# CM3_HDMI.net
KiCad netlist of a schematic drawn in Altium Designer
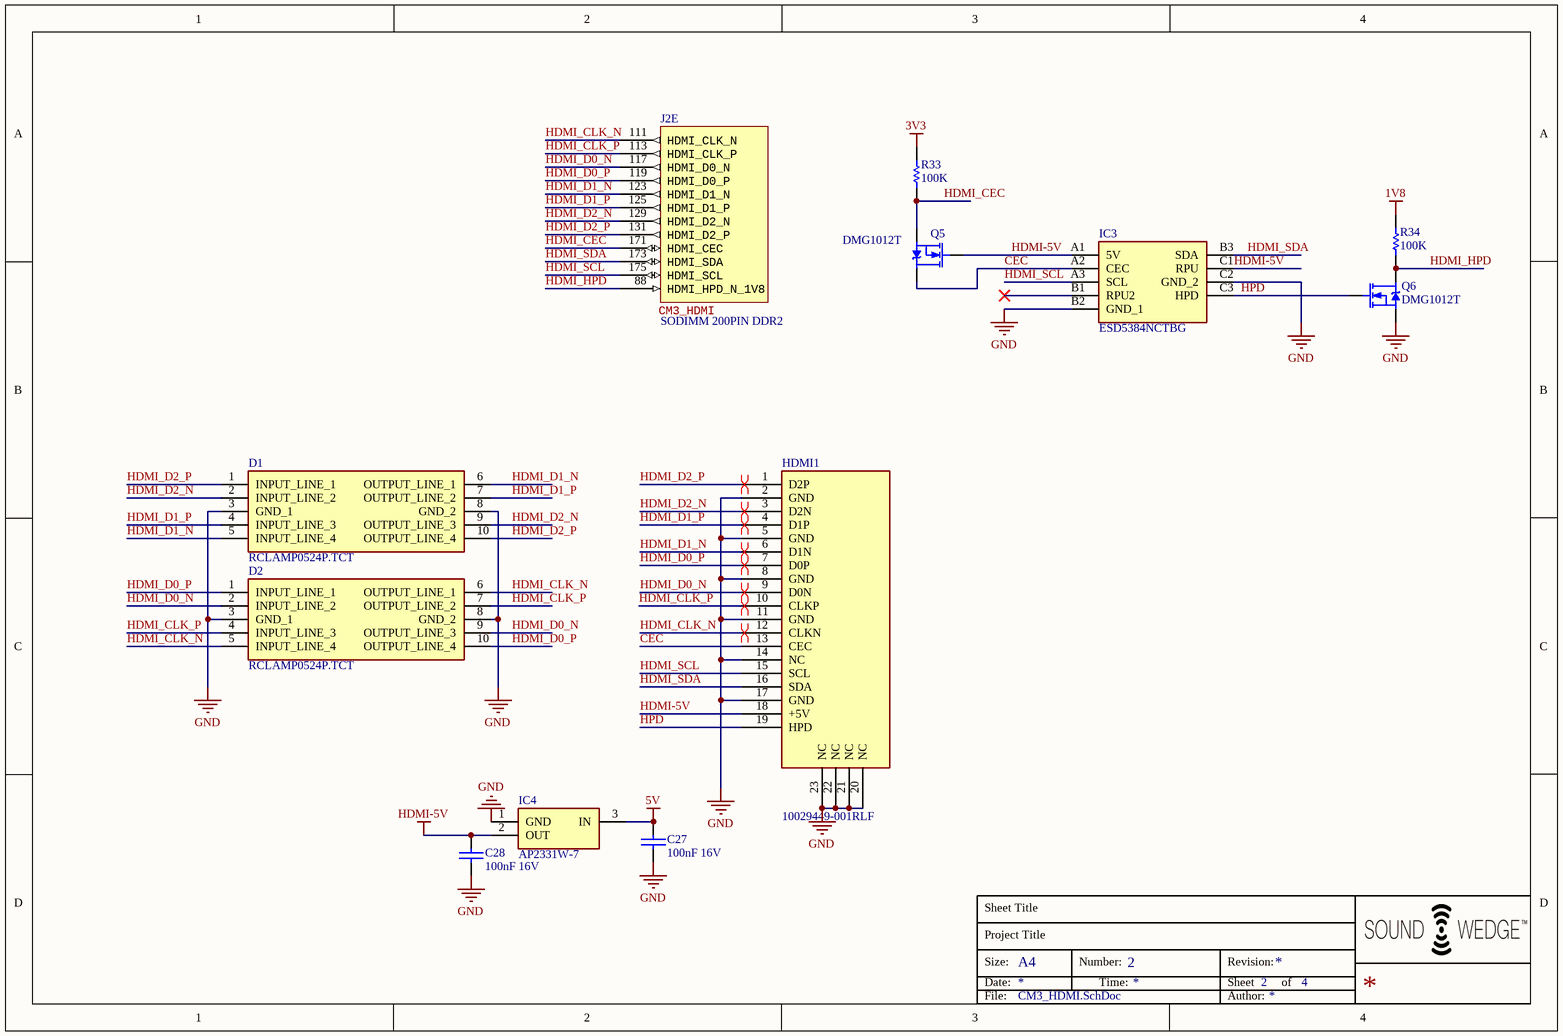
[diagram p0: CM3_HDMI.SchDoc]

(export (version "E")
  (design (tool "Eeschema 10.0.6"))
  (components
    (comp (ref "C27") (value "100nF 16V") (footprint "PCB_VPlayer:0402C") (libsource (lib "电容") (part "CAP")))
    (comp (ref "C28") (value "100nF 16V") (footprint "PCB_VPlayer:0402C") (libsource (lib "电容") (part "CAP")))
    (comp (ref "D1")
      (value "RCLAMP0524P.TCT")
      (footprint "SamacSys:RCLAMP0524P")
      (description "Diode")
      (fields (field (name "MOUSER PART NUMBER") "947-RCLAMP0524P.TCT"))
      (libsource (lib "*") (part "RCLAMP0524P.TCT"))
    )
    (comp (ref "D2")
      (value "RCLAMP0524P.TCT")
      (footprint "SamacSys:RCLAMP0524P")
      (description "Diode")
      (fields (field (name "MOUSER PART NUMBER") "947-RCLAMP0524P.TCT"))
      (libsource (lib "*") (part "RCLAMP0524P.TCT"))
    )
    (comp (ref "HDMI1")
      (value "10029449-001RLF")
      (footprint "HDMI-001")
      (description "HDMI Connector")
      (fields
        (field (name "MOUSER PART NUMBER") "649-10029449-001RLF")
        (field (name "RS PART NUMBER") "7710094")
      )
      (libsource (lib "音视频插座") (part "10029449-001RLF"))
    )
    (comp (ref "IC3")
      (value "ESD5384NCTBG")
      (footprint "SamacSys:BGA9C40P3X3_114X114X63")
      (description "Integrated Circuit")
      (fields
        (field (name "MOUSER PART NUMBER") "863-ESD5384NCTBG")
        (field (name "RS PART NUMBER") "8010213P")
      )
      (libsource (lib "*") (part "ESD5384NCTBG"))
    )
    (comp (ref "IC4")
      (value "AP2331W-7")
      (footprint "SamacSys:SOT95P285X130-3N")
      (description "Integrated Circuit")
      (fields (field (name "MOUSER PART NUMBER") "621-AP2331W-7") (field (name "RS PART NUMBER") "8287665P"))
      (libsource (lib "*") (part "AP2331W-7"))
    )
    (comp (ref "J2")
      (value "SODIMM 200PIN DDR2")
      (footprint "树莓派模块:SODIMM 200PIN - 5.2H")
      (libsource (lib "树莓派模块") (part "RPi-CM3"))
    )
    (comp (ref "Q5")
      (value "DMG1012T")
      (footprint "SOT523")
      (description "N沟道场效应管")
      (libsource (lib "MOS管") (part "N-MOS"))
    )
    (comp (ref "Q6")
      (value "DMG1012T")
      (footprint "SOT523")
      (description "N沟道场效应管")
      (libsource (lib "MOS管") (part "N-MOS"))
    )
    (comp (ref "R33") (value "100K") (footprint "PCB_VPlayer:0402R") (libsource (lib "电阻") (part "RES")))
    (comp (ref "R34") (value "100K") (footprint "PCB_VPlayer:0402R") (libsource (lib "电阻") (part "RES")))
  )
  (nets
    (net (code "1") (name "/CEC") (class "Default")
      (node (ref "HDMI1") (pin "13") (pinfunction "CEC_13") (pintype "passive"))
      (node (ref "IC3") (pin "A2") (pinfunction "CEC_A2") (pintype "passive"))
      (node (ref "Q5") (pin "D") (pinfunction "D_D") (pintype "passive"))
    )
    (net (code "2") (name "/HDMI_CEC") (class "Default")
      (node (ref "J2") (pin "171") (pinfunction "HDMI_CEC_171") (pintype "bidirectional"))
      (node (ref "Q5") (pin "S") (pinfunction "S_S") (pintype "passive"))
      (node (ref "R33") (pin "1") (pinfunction "1_1") (pintype "passive"))
    )
    (net (code "3") (name "/HDMI_CLK_N") (class "Default")
      (node (ref "D2") (pin "5") (pinfunction "INPUT_LINE_4_5") (pintype "passive"))
      (node (ref "D2") (pin "6") (pinfunction "OUTPUT_LINE_1_6") (pintype "passive"))
      (node (ref "HDMI1") (pin "12") (pinfunction "CLKN_12") (pintype "passive"))
      (node (ref "J2") (pin "111") (pinfunction "HDMI_CLK_N_111") (pintype "output"))
    )
    (net (code "4") (name "/HDMI_CLK_P") (class "Default")
      (node (ref "D2") (pin "4") (pinfunction "INPUT_LINE_3_4") (pintype "passive"))
      (node (ref "D2") (pin "7") (pinfunction "OUTPUT_LINE_2_7") (pintype "passive"))
      (node (ref "HDMI1") (pin "10") (pinfunction "CLKP_10") (pintype "passive"))
      (node (ref "J2") (pin "113") (pinfunction "HDMI_CLK_P_113") (pintype "output"))
    )
    (net (code "5") (name "/HDMI_D0_N") (class "Default")
      (node (ref "D2") (pin "2") (pinfunction "INPUT_LINE_2_2") (pintype "passive"))
      (node (ref "D2") (pin "9") (pinfunction "OUTPUT_LINE_3_9") (pintype "passive"))
      (node (ref "HDMI1") (pin "9") (pinfunction "D0N_9") (pintype "passive"))
      (node (ref "J2") (pin "117") (pinfunction "HDMI_D0_N_117") (pintype "output"))
    )
    (net (code "6") (name "/HDMI_D0_P") (class "Default")
      (node (ref "D2") (pin "1") (pinfunction "INPUT_LINE_1_1") (pintype "passive"))
      (node (ref "D2") (pin "10") (pinfunction "OUTPUT_LINE_4_10") (pintype "passive"))
      (node (ref "HDMI1") (pin "7") (pinfunction "D0P_7") (pintype "passive"))
      (node (ref "J2") (pin "119") (pinfunction "HDMI_D0_P_119") (pintype "output"))
    )
    (net (code "7") (name "/HDMI_D1_N") (class "Default")
      (node (ref "D1") (pin "5") (pinfunction "INPUT_LINE_4_5") (pintype "passive"))
      (node (ref "D1") (pin "6") (pinfunction "OUTPUT_LINE_1_6") (pintype "passive"))
      (node (ref "HDMI1") (pin "6") (pinfunction "D1N_6") (pintype "passive"))
      (node (ref "J2") (pin "123") (pinfunction "HDMI_D1_N_123") (pintype "output"))
    )
    (net (code "8") (name "/HDMI_D1_P") (class "Default")
      (node (ref "D1") (pin "4") (pinfunction "INPUT_LINE_3_4") (pintype "passive"))
      (node (ref "D1") (pin "7") (pinfunction "OUTPUT_LINE_2_7") (pintype "passive"))
      (node (ref "HDMI1") (pin "4") (pinfunction "D1P_4") (pintype "passive"))
      (node (ref "J2") (pin "125") (pinfunction "HDMI_D1_P_125") (pintype "output"))
    )
    (net (code "9") (name "/HDMI_D2_N") (class "Default")
      (node (ref "D1") (pin "2") (pinfunction "INPUT_LINE_2_2") (pintype "passive"))
      (node (ref "D1") (pin "9") (pinfunction "OUTPUT_LINE_3_9") (pintype "passive"))
      (node (ref "HDMI1") (pin "3") (pinfunction "D2N_3") (pintype "passive"))
      (node (ref "J2") (pin "129") (pinfunction "HDMI_D2_N_129") (pintype "output"))
    )
    (net (code "10") (name "/HDMI_D2_P") (class "Default")
      (node (ref "D1") (pin "1") (pinfunction "INPUT_LINE_1_1") (pintype "passive"))
      (node (ref "D1") (pin "10") (pinfunction "OUTPUT_LINE_4_10") (pintype "passive"))
      (node (ref "HDMI1") (pin "1") (pinfunction "D2P_1") (pintype "passive"))
      (node (ref "J2") (pin "131") (pinfunction "HDMI_D2_P_131") (pintype "output"))
    )
    (net (code "11") (name "/HDMI_HPD") (class "Default")
      (node (ref "J2") (pin "88") (pinfunction "HDMI_HPD_N_1V8_88") (pintype "input"))
      (node (ref "Q6") (pin "D") (pinfunction "D_D") (pintype "passive"))
      (node (ref "R34") (pin "1") (pinfunction "1_1") (pintype "passive"))
    )
    (net (code "12") (name "/HDMI_SCL") (class "Default")
      (node (ref "HDMI1") (pin "15") (pinfunction "SCL_15") (pintype "passive"))
      (node (ref "IC3") (pin "A3") (pinfunction "SCL_A3") (pintype "passive"))
      (node (ref "J2") (pin "175") (pinfunction "HDMI_SCL_175") (pintype "bidirectional"))
    )
    (net (code "13") (name "/HDMI_SDA") (class "Default")
      (node (ref "HDMI1") (pin "16") (pinfunction "SDA_16") (pintype "passive"))
      (node (ref "IC3") (pin "B3") (pinfunction "SDA_B3") (pintype "passive"))
      (node (ref "J2") (pin "173") (pinfunction "HDMI_SDA_173") (pintype "bidirectional"))
    )
    (net (code "14") (name "/HPD") (class "Default")
      (node (ref "HDMI1") (pin "19") (pinfunction "HPD_19") (pintype "passive"))
      (node (ref "IC3") (pin "C3") (pinfunction "HPD_C3") (pintype "passive"))
      (node (ref "Q6") (pin "G") (pinfunction "G_G") (pintype "passive"))
    )
    (net (code "15") (name "1V8") (class "Default")
      (node (ref "R34") (pin "2") (pinfunction "2_2") (pintype "passive"))
    )
    (net (code "16") (name "3V3") (class "Default")
      (node (ref "R33") (pin "2") (pinfunction "2_2") (pintype "passive"))
    )
    (net (code "17") (name "5V") (class "Default")
      (node (ref "C27") (pin "1") (pinfunction "1_1") (pintype "passive"))
      (node (ref "IC4") (pin "3") (pinfunction "IN_3") (pintype "passive"))
    )
    (net (code "18") (name "GND") (class "Default")
      (node (ref "C27") (pin "2") (pinfunction "2_2") (pintype "passive"))
      (node (ref "C28") (pin "2") (pinfunction "2_2") (pintype "passive"))
      (node (ref "D1") (pin "3") (pinfunction "GND_1_3") (pintype "passive"))
      (node (ref "D1") (pin "8") (pinfunction "GND_2_8") (pintype "passive"))
      (node (ref "D2") (pin "3") (pinfunction "GND_1_3") (pintype "passive"))
      (node (ref "D2") (pin "8") (pinfunction "GND_2_8") (pintype "passive"))
      (node (ref "HDMI1") (pin "11") (pinfunction "GND_11") (pintype "passive"))
      (node (ref "HDMI1") (pin "14") (pinfunction "NC_14") (pintype "passive"))
      (node (ref "HDMI1") (pin "17") (pinfunction "GND_17") (pintype "passive"))
      (node (ref "HDMI1") (pin "2") (pinfunction "GND_2") (pintype "passive"))
      (node (ref "HDMI1") (pin "20") (pinfunction "NC_20") (pintype "passive"))
      (node (ref "HDMI1") (pin "21") (pinfunction "NC_21") (pintype "passive"))
      (node (ref "HDMI1") (pin "22") (pinfunction "NC_22") (pintype "passive"))
      (node (ref "HDMI1") (pin "23") (pinfunction "NC_23") (pintype "passive"))
      (node (ref "HDMI1") (pin "5") (pinfunction "GND_5") (pintype "passive"))
      (node (ref "HDMI1") (pin "8") (pinfunction "GND_8") (pintype "passive"))
      (node (ref "IC3") (pin "B2") (pinfunction "GND_1_B2") (pintype "power_in"))
      (node (ref "IC3") (pin "C2") (pinfunction "GND_2_C2") (pintype "power_in"))
      (node (ref "IC4") (pin "1") (pinfunction "GND_1") (pintype "passive"))
      (node (ref "Q6") (pin "S") (pinfunction "S_S") (pintype "passive"))
    )
    (net (code "19") (name "HDMI-5V") (class "Default")
      (node (ref "C28") (pin "1") (pinfunction "1_1") (pintype "passive"))
      (node (ref "HDMI1") (pin "18") (pinfunction "+5V_18") (pintype "passive"))
      (node (ref "IC3") (pin "A1") (pinfunction "5V_A1") (pintype "passive"))
      (node (ref "IC3") (pin "C1") (pinfunction "RPU_C1") (pintype "passive"))
      (node (ref "IC4") (pin "2") (pinfunction "OUT_2") (pintype "passive"))
      (node (ref "Q5") (pin "G") (pinfunction "G_G") (pintype "passive"))
    )
    (net (code "20") (name "unconnected-(IC3-RPU2-PadB1)") (class "Default")
      (node (ref "IC3") (pin "B1") (pinfunction "RPU2_B1") (pintype "passive+no_connect"))
    )
  )
)
